# RS232_2xNPN_Alt.net
KiCad netlist of a schematic drawn in EAGLE
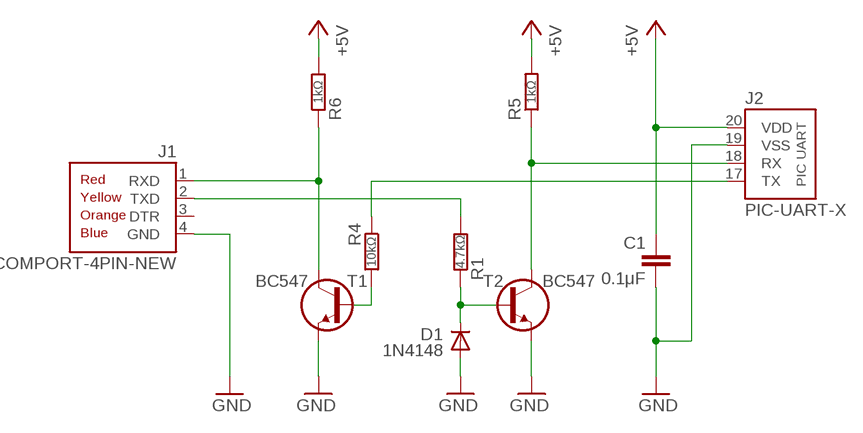
[diagram p0: schematic, sheet 1]

(export (version "E")
  (design (tool "Eeschema 10.0.6"))
  (components
    (comp (ref "C1")
      (value "0.1μF")
      (footprint "eagle-import:C025-015X024")
      (libsource (lib "eagle-import") (part "C025-015X024"))
    )
    (comp (ref "D1")
      (value "1N4148")
      (footprint "eagle-import:DO34-7")
      (libsource (lib "eagle-import") (part "1N414834-7"))
    )
    (comp (ref "J1")
      (value "COMPORT-4PIN-NEW")
      (footprint "eagle-import:RS232-4PIN-NEW")
      (libsource (lib "eagle-import") (part "COMPORT-4PIN-NEW"))
    )
    (comp (ref "J2")
      (value "PIC-UART-X")
      (footprint "eagle-import:PIC-UART-X")
      (libsource (lib "eagle-import") (part "PIC-UART-X"))
    )
    (comp (ref "R1")
      (value "4.7kΩ")
      (footprint "eagle-import:0202_7")
      (libsource (lib "eagle-import") (part "R0202/7"))
    )
    (comp (ref "R4")
      (value "10kΩ")
      (footprint "eagle-import:0204_7-V")
      (libsource (lib "eagle-import") (part "R0204/7-V"))
    )
    (comp (ref "R5")
      (value "1kΩ")
      (footprint "eagle-import:0204_7-V")
      (libsource (lib "eagle-import") (part "R0204/7-V"))
    )
    (comp (ref "R6")
      (value "1kΩ")
      (footprint "eagle-import:0204_7")
      (libsource (lib "eagle-import") (part "R0204/7"))
    )
    (comp (ref "T1")
      (value "BC547")
      (footprint "eagle-import:TO92-CBE")
      (libsource (lib "eagle-import") (part "BC547CBE"))
    )
    (comp (ref "T2")
      (value "BC547")
      (footprint "eagle-import:TO92-CBE")
      (libsource (lib "eagle-import") (part "BC547CBE"))
    )
  )
  (nets
    (net (code "1") (name "+5V") (class "Default")
      (node (ref "C1") (pin "1") (pinfunction "1_1") (pintype "passive"))
      (node (ref "J2") (pin "20") (pinfunction "VDD_20") (pintype "passive"))
      (node (ref "R5") (pin "2") (pinfunction "2_2") (pintype "passive"))
      (node (ref "R6") (pin "2") (pinfunction "2_2") (pintype "passive"))
    )
    (net (code "2") (name "GND") (class "Default")
      (node (ref "C1") (pin "2") (pinfunction "2_2") (pintype "passive"))
      (node (ref "D1") (pin "A") (pinfunction "A_A") (pintype "passive"))
      (node (ref "J1") (pin "4") (pinfunction "GND_4") (pintype "passive"))
      (node (ref "J2") (pin "19") (pinfunction "VSS_19") (pintype "passive"))
      (node (ref "T1") (pin "E") (pinfunction "E_E") (pintype "passive"))
      (node (ref "T2") (pin "E") (pinfunction "E_E") (pintype "passive"))
    )
    (net (code "3") (name "Net-(D1-PadC)") (class "Default")
      (node (ref "D1") (pin "C") (pinfunction "C_C") (pintype "passive"))
      (node (ref "R1") (pin "1") (pinfunction "1_1") (pintype "passive"))
      (node (ref "T2") (pin "B") (pinfunction "B_B") (pintype "passive"))
    )
    (net (code "4") (name "Net-(J1-RXD)") (class "Default")
      (node (ref "J1") (pin "1") (pinfunction "RXD_1") (pintype "passive"))
      (node (ref "R6") (pin "1") (pinfunction "1_1") (pintype "passive"))
      (node (ref "T1") (pin "C") (pinfunction "C_C") (pintype "passive"))
    )
    (net (code "5") (name "Net-(J1-TXD)") (class "Default")
      (node (ref "J1") (pin "2") (pinfunction "TXD_2") (pintype "passive"))
      (node (ref "R1") (pin "2") (pinfunction "2_2") (pintype "passive"))
    )
    (net (code "6") (name "Net-(J2-RX)") (class "Default")
      (node (ref "J2") (pin "18") (pinfunction "RX_18") (pintype "passive"))
      (node (ref "R5") (pin "1") (pinfunction "1_1") (pintype "passive"))
      (node (ref "T2") (pin "C") (pinfunction "C_C") (pintype "passive"))
    )
    (net (code "7") (name "Net-(J2-TX)") (class "Default")
      (node (ref "J2") (pin "17") (pinfunction "TX_17") (pintype "passive"))
      (node (ref "R4") (pin "1") (pinfunction "1_1") (pintype "passive"))
    )
    (net (code "8") (name "Net-(R4-Pad2)") (class "Default")
      (node (ref "R4") (pin "2") (pinfunction "2_2") (pintype "passive"))
      (node (ref "T1") (pin "B") (pinfunction "B_B") (pintype "passive"))
    )
    (net (code "9") (name "unconnected-(J1-DTR-Pad3)") (class "Default")
      (node (ref "J1") (pin "3") (pinfunction "DTR_3") (pintype "passive"))
    )
  )
)
